# led_matrix_v_1_0.net
KiCad netlist of a schematic drawn in EAGLE
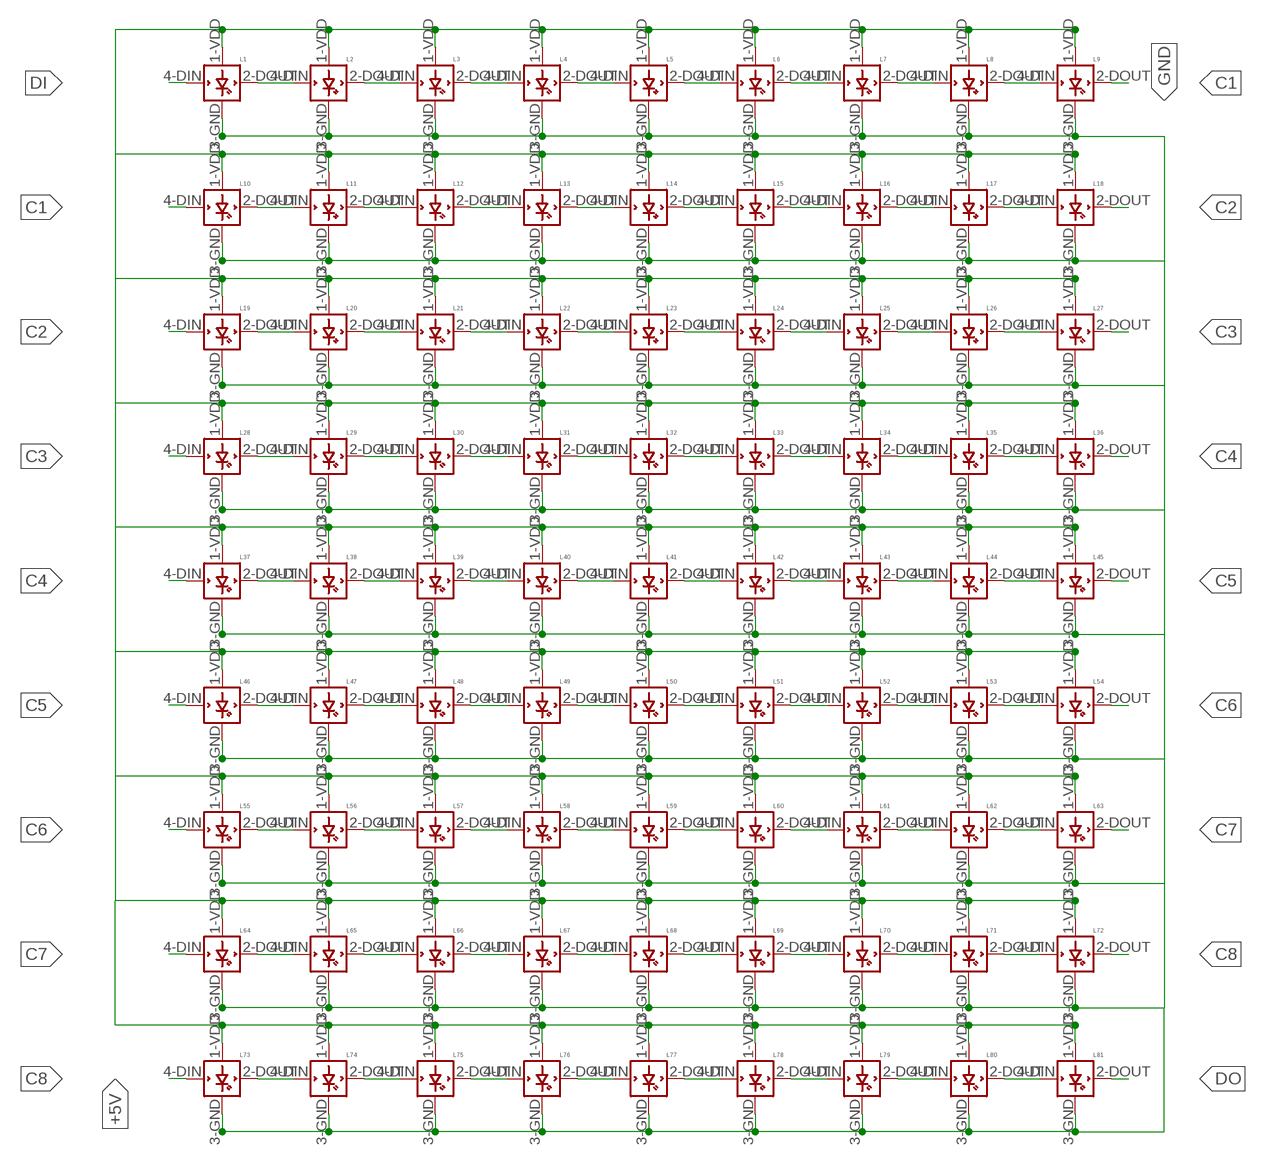
[diagram p0: schematic, sheet 1]

(export (version "E")
  (design (tool "Eeschema 10.0.6"))
  (components
    (comp (ref "L1")
      (value "WS2812B")
      (footprint "eagle-import:WS2812B")
      (libsource (lib "eagle-import") (part "WS2812B"))
    )
    (comp (ref "L2")
      (value "WS2812B")
      (footprint "eagle-import:WS2812B")
      (libsource (lib "eagle-import") (part "WS2812B"))
    )
    (comp (ref "L3")
      (value "WS2812B")
      (footprint "eagle-import:WS2812B")
      (libsource (lib "eagle-import") (part "WS2812B"))
    )
    (comp (ref "L4")
      (value "WS2812B")
      (footprint "eagle-import:WS2812B")
      (libsource (lib "eagle-import") (part "WS2812B"))
    )
    (comp (ref "L5")
      (value "WS2812B")
      (footprint "eagle-import:WS2812B")
      (libsource (lib "eagle-import") (part "WS2812B"))
    )
    (comp (ref "L6")
      (value "WS2812B")
      (footprint "eagle-import:WS2812B")
      (libsource (lib "eagle-import") (part "WS2812B"))
    )
    (comp (ref "L7")
      (value "WS2812B")
      (footprint "eagle-import:WS2812B")
      (libsource (lib "eagle-import") (part "WS2812B"))
    )
    (comp (ref "L8")
      (value "WS2812B")
      (footprint "eagle-import:WS2812B")
      (libsource (lib "eagle-import") (part "WS2812B"))
    )
    (comp (ref "L9")
      (value "WS2812B")
      (footprint "eagle-import:WS2812B")
      (libsource (lib "eagle-import") (part "WS2812B"))
    )
    (comp (ref "L10")
      (value "WS2812B")
      (footprint "eagle-import:WS2812B")
      (libsource (lib "eagle-import") (part "WS2812B"))
    )
    (comp (ref "L11")
      (value "WS2812B")
      (footprint "eagle-import:WS2812B")
      (libsource (lib "eagle-import") (part "WS2812B"))
    )
    (comp (ref "L12")
      (value "WS2812B")
      (footprint "eagle-import:WS2812B")
      (libsource (lib "eagle-import") (part "WS2812B"))
    )
    (comp (ref "L13")
      (value "WS2812B")
      (footprint "eagle-import:WS2812B")
      (libsource (lib "eagle-import") (part "WS2812B"))
    )
    (comp (ref "L14")
      (value "WS2812B")
      (footprint "eagle-import:WS2812B")
      (libsource (lib "eagle-import") (part "WS2812B"))
    )
    (comp (ref "L15")
      (value "WS2812B")
      (footprint "eagle-import:WS2812B")
      (libsource (lib "eagle-import") (part "WS2812B"))
    )
    (comp (ref "L16")
      (value "WS2812B")
      (footprint "eagle-import:WS2812B")
      (libsource (lib "eagle-import") (part "WS2812B"))
    )
    (comp (ref "L17")
      (value "WS2812B")
      (footprint "eagle-import:WS2812B")
      (libsource (lib "eagle-import") (part "WS2812B"))
    )
    (comp (ref "L18")
      (value "WS2812B")
      (footprint "eagle-import:WS2812B")
      (libsource (lib "eagle-import") (part "WS2812B"))
    )
    (comp (ref "L19")
      (value "WS2812B")
      (footprint "eagle-import:WS2812B")
      (libsource (lib "eagle-import") (part "WS2812B"))
    )
    (comp (ref "L20")
      (value "WS2812B")
      (footprint "eagle-import:WS2812B")
      (libsource (lib "eagle-import") (part "WS2812B"))
    )
    (comp (ref "L21")
      (value "WS2812B")
      (footprint "eagle-import:WS2812B")
      (libsource (lib "eagle-import") (part "WS2812B"))
    )
    (comp (ref "L22")
      (value "WS2812B")
      (footprint "eagle-import:WS2812B")
      (libsource (lib "eagle-import") (part "WS2812B"))
    )
    (comp (ref "L23")
      (value "WS2812B")
      (footprint "eagle-import:WS2812B")
      (libsource (lib "eagle-import") (part "WS2812B"))
    )
    (comp (ref "L24")
      (value "WS2812B")
      (footprint "eagle-import:WS2812B")
      (libsource (lib "eagle-import") (part "WS2812B"))
    )
    (comp (ref "L25")
      (value "WS2812B")
      (footprint "eagle-import:WS2812B")
      (libsource (lib "eagle-import") (part "WS2812B"))
    )
    (comp (ref "L26")
      (value "WS2812B")
      (footprint "eagle-import:WS2812B")
      (libsource (lib "eagle-import") (part "WS2812B"))
    )
    (comp (ref "L27")
      (value "WS2812B")
      (footprint "eagle-import:WS2812B")
      (libsource (lib "eagle-import") (part "WS2812B"))
    )
    (comp (ref "L28")
      (value "WS2812B")
      (footprint "eagle-import:WS2812B")
      (libsource (lib "eagle-import") (part "WS2812B"))
    )
    (comp (ref "L29")
      (value "WS2812B")
      (footprint "eagle-import:WS2812B")
      (libsource (lib "eagle-import") (part "WS2812B"))
    )
    (comp (ref "L30")
      (value "WS2812B")
      (footprint "eagle-import:WS2812B")
      (libsource (lib "eagle-import") (part "WS2812B"))
    )
    (comp (ref "L31")
      (value "WS2812B")
      (footprint "eagle-import:WS2812B")
      (libsource (lib "eagle-import") (part "WS2812B"))
    )
    (comp (ref "L32")
      (value "WS2812B")
      (footprint "eagle-import:WS2812B")
      (libsource (lib "eagle-import") (part "WS2812B"))
    )
    (comp (ref "L33")
      (value "WS2812B")
      (footprint "eagle-import:WS2812B")
      (libsource (lib "eagle-import") (part "WS2812B"))
    )
    (comp (ref "L34")
      (value "WS2812B")
      (footprint "eagle-import:WS2812B")
      (libsource (lib "eagle-import") (part "WS2812B"))
    )
    (comp (ref "L35")
      (value "WS2812B")
      (footprint "eagle-import:WS2812B")
      (libsource (lib "eagle-import") (part "WS2812B"))
    )
    (comp (ref "L36")
      (value "WS2812B")
      (footprint "eagle-import:WS2812B")
      (libsource (lib "eagle-import") (part "WS2812B"))
    )
    (comp (ref "L37")
      (value "WS2812B")
      (footprint "eagle-import:WS2812B")
      (libsource (lib "eagle-import") (part "WS2812B"))
    )
    (comp (ref "L38")
      (value "WS2812B")
      (footprint "eagle-import:WS2812B")
      (libsource (lib "eagle-import") (part "WS2812B"))
    )
    (comp (ref "L39")
      (value "WS2812B")
      (footprint "eagle-import:WS2812B")
      (libsource (lib "eagle-import") (part "WS2812B"))
    )
    (comp (ref "L40")
      (value "WS2812B")
      (footprint "eagle-import:WS2812B")
      (libsource (lib "eagle-import") (part "WS2812B"))
    )
    (comp (ref "L41")
      (value "WS2812B")
      (footprint "eagle-import:WS2812B")
      (libsource (lib "eagle-import") (part "WS2812B"))
    )
    (comp (ref "L42")
      (value "WS2812B")
      (footprint "eagle-import:WS2812B")
      (libsource (lib "eagle-import") (part "WS2812B"))
    )
    (comp (ref "L43")
      (value "WS2812B")
      (footprint "eagle-import:WS2812B")
      (libsource (lib "eagle-import") (part "WS2812B"))
    )
    (comp (ref "L44")
      (value "WS2812B")
      (footprint "eagle-import:WS2812B")
      (libsource (lib "eagle-import") (part "WS2812B"))
    )
    (comp (ref "L45")
      (value "WS2812B")
      (footprint "eagle-import:WS2812B")
      (libsource (lib "eagle-import") (part "WS2812B"))
    )
    (comp (ref "L46")
      (value "WS2812B")
      (footprint "eagle-import:WS2812B")
      (libsource (lib "eagle-import") (part "WS2812B"))
    )
    (comp (ref "L47")
      (value "WS2812B")
      (footprint "eagle-import:WS2812B")
      (libsource (lib "eagle-import") (part "WS2812B"))
    )
    (comp (ref "L48")
      (value "WS2812B")
      (footprint "eagle-import:WS2812B")
      (libsource (lib "eagle-import") (part "WS2812B"))
    )
    (comp (ref "L49")
      (value "WS2812B")
      (footprint "eagle-import:WS2812B")
      (libsource (lib "eagle-import") (part "WS2812B"))
    )
    (comp (ref "L50")
      (value "WS2812B")
      (footprint "eagle-import:WS2812B")
      (libsource (lib "eagle-import") (part "WS2812B"))
    )
    (comp (ref "L51")
      (value "WS2812B")
      (footprint "eagle-import:WS2812B")
      (libsource (lib "eagle-import") (part "WS2812B"))
    )
    (comp (ref "L52")
      (value "WS2812B")
      (footprint "eagle-import:WS2812B")
      (libsource (lib "eagle-import") (part "WS2812B"))
    )
    (comp (ref "L53")
      (value "WS2812B")
      (footprint "eagle-import:WS2812B")
      (libsource (lib "eagle-import") (part "WS2812B"))
    )
    (comp (ref "L54")
      (value "WS2812B")
      (footprint "eagle-import:WS2812B")
      (libsource (lib "eagle-import") (part "WS2812B"))
    )
    (comp (ref "L55")
      (value "WS2812B")
      (footprint "eagle-import:WS2812B")
      (libsource (lib "eagle-import") (part "WS2812B"))
    )
    (comp (ref "L56")
      (value "WS2812B")
      (footprint "eagle-import:WS2812B")
      (libsource (lib "eagle-import") (part "WS2812B"))
    )
    (comp (ref "L57")
      (value "WS2812B")
      (footprint "eagle-import:WS2812B")
      (libsource (lib "eagle-import") (part "WS2812B"))
    )
    (comp (ref "L58")
      (value "WS2812B")
      (footprint "eagle-import:WS2812B")
      (libsource (lib "eagle-import") (part "WS2812B"))
    )
    (comp (ref "L59")
      (value "WS2812B")
      (footprint "eagle-import:WS2812B")
      (libsource (lib "eagle-import") (part "WS2812B"))
    )
    (comp (ref "L60")
      (value "WS2812B")
      (footprint "eagle-import:WS2812B")
      (libsource (lib "eagle-import") (part "WS2812B"))
    )
    (comp (ref "L61")
      (value "WS2812B")
      (footprint "eagle-import:WS2812B")
      (libsource (lib "eagle-import") (part "WS2812B"))
    )
    (comp (ref "L62")
      (value "WS2812B")
      (footprint "eagle-import:WS2812B")
      (libsource (lib "eagle-import") (part "WS2812B"))
    )
    (comp (ref "L63")
      (value "WS2812B")
      (footprint "eagle-import:WS2812B")
      (libsource (lib "eagle-import") (part "WS2812B"))
    )
    (comp (ref "L64")
      (value "WS2812B")
      (footprint "eagle-import:WS2812B")
      (libsource (lib "eagle-import") (part "WS2812B"))
    )
    (comp (ref "L65")
      (value "WS2812B")
      (footprint "eagle-import:WS2812B")
      (libsource (lib "eagle-import") (part "WS2812B"))
    )
    (comp (ref "L66")
      (value "WS2812B")
      (footprint "eagle-import:WS2812B")
      (libsource (lib "eagle-import") (part "WS2812B"))
    )
    (comp (ref "L67")
      (value "WS2812B")
      (footprint "eagle-import:WS2812B")
      (libsource (lib "eagle-import") (part "WS2812B"))
    )
    (comp (ref "L68")
      (value "WS2812B")
      (footprint "eagle-import:WS2812B")
      (libsource (lib "eagle-import") (part "WS2812B"))
    )
    (comp (ref "L69")
      (value "WS2812B")
      (footprint "eagle-import:WS2812B")
      (libsource (lib "eagle-import") (part "WS2812B"))
    )
    (comp (ref "L70")
      (value "WS2812B")
      (footprint "eagle-import:WS2812B")
      (libsource (lib "eagle-import") (part "WS2812B"))
    )
    (comp (ref "L71")
      (value "WS2812B")
      (footprint "eagle-import:WS2812B")
      (libsource (lib "eagle-import") (part "WS2812B"))
    )
    (comp (ref "L72")
      (value "WS2812B")
      (footprint "eagle-import:WS2812B")
      (libsource (lib "eagle-import") (part "WS2812B"))
    )
    (comp (ref "L73")
      (value "WS2812B")
      (footprint "eagle-import:WS2812B")
      (libsource (lib "eagle-import") (part "WS2812B"))
    )
    (comp (ref "L74")
      (value "WS2812B")
      (footprint "eagle-import:WS2812B")
      (libsource (lib "eagle-import") (part "WS2812B"))
    )
    (comp (ref "L75")
      (value "WS2812B")
      (footprint "eagle-import:WS2812B")
      (libsource (lib "eagle-import") (part "WS2812B"))
    )
    (comp (ref "L76")
      (value "WS2812B")
      (footprint "eagle-import:WS2812B")
      (libsource (lib "eagle-import") (part "WS2812B"))
    )
    (comp (ref "L77")
      (value "WS2812B")
      (footprint "eagle-import:WS2812B")
      (libsource (lib "eagle-import") (part "WS2812B"))
    )
    (comp (ref "L78")
      (value "WS2812B")
      (footprint "eagle-import:WS2812B")
      (libsource (lib "eagle-import") (part "WS2812B"))
    )
    (comp (ref "L79")
      (value "WS2812B")
      (footprint "eagle-import:WS2812B")
      (libsource (lib "eagle-import") (part "WS2812B"))
    )
    (comp (ref "L80")
      (value "WS2812B")
      (footprint "eagle-import:WS2812B")
      (libsource (lib "eagle-import") (part "WS2812B"))
    )
    (comp (ref "L81")
      (value "WS2812B")
      (footprint "eagle-import:WS2812B")
      (libsource (lib "eagle-import") (part "WS2812B"))
    )
  )
  (nets
    (net (code "1") (name "+5V") (class "Default")
      (node (ref "L1") (pin "1-VDD") (pinfunction "VDD_1-VDD") (pintype "bidirectional"))
      (node (ref "L10") (pin "1-VDD") (pinfunction "VDD_1-VDD") (pintype "bidirectional"))
      (node (ref "L11") (pin "1-VDD") (pinfunction "VDD_1-VDD") (pintype "bidirectional"))
      (node (ref "L12") (pin "1-VDD") (pinfunction "VDD_1-VDD") (pintype "bidirectional"))
      (node (ref "L13") (pin "1-VDD") (pinfunction "VDD_1-VDD") (pintype "bidirectional"))
      (node (ref "L14") (pin "1-VDD") (pinfunction "VDD_1-VDD") (pintype "bidirectional"))
      (node (ref "L15") (pin "1-VDD") (pinfunction "VDD_1-VDD") (pintype "bidirectional"))
      (node (ref "L16") (pin "1-VDD") (pinfunction "VDD_1-VDD") (pintype "bidirectional"))
      (node (ref "L17") (pin "1-VDD") (pinfunction "VDD_1-VDD") (pintype "bidirectional"))
      (node (ref "L18") (pin "1-VDD") (pinfunction "VDD_1-VDD") (pintype "bidirectional"))
      (node (ref "L19") (pin "1-VDD") (pinfunction "VDD_1-VDD") (pintype "bidirectional"))
      (node (ref "L2") (pin "1-VDD") (pinfunction "VDD_1-VDD") (pintype "bidirectional"))
      (node (ref "L20") (pin "1-VDD") (pinfunction "VDD_1-VDD") (pintype "bidirectional"))
      (node (ref "L21") (pin "1-VDD") (pinfunction "VDD_1-VDD") (pintype "bidirectional"))
      (node (ref "L22") (pin "1-VDD") (pinfunction "VDD_1-VDD") (pintype "bidirectional"))
      (node (ref "L23") (pin "1-VDD") (pinfunction "VDD_1-VDD") (pintype "bidirectional"))
      (node (ref "L24") (pin "1-VDD") (pinfunction "VDD_1-VDD") (pintype "bidirectional"))
      (node (ref "L25") (pin "1-VDD") (pinfunction "VDD_1-VDD") (pintype "bidirectional"))
      (node (ref "L26") (pin "1-VDD") (pinfunction "VDD_1-VDD") (pintype "bidirectional"))
      (node (ref "L27") (pin "1-VDD") (pinfunction "VDD_1-VDD") (pintype "bidirectional"))
      (node (ref "L28") (pin "1-VDD") (pinfunction "VDD_1-VDD") (pintype "bidirectional"))
      (node (ref "L29") (pin "1-VDD") (pinfunction "VDD_1-VDD") (pintype "bidirectional"))
      (node (ref "L3") (pin "1-VDD") (pinfunction "VDD_1-VDD") (pintype "bidirectional"))
      (node (ref "L30") (pin "1-VDD") (pinfunction "VDD_1-VDD") (pintype "bidirectional"))
      (node (ref "L31") (pin "1-VDD") (pinfunction "VDD_1-VDD") (pintype "bidirectional"))
      (node (ref "L32") (pin "1-VDD") (pinfunction "VDD_1-VDD") (pintype "bidirectional"))
      (node (ref "L33") (pin "1-VDD") (pinfunction "VDD_1-VDD") (pintype "bidirectional"))
      (node (ref "L34") (pin "1-VDD") (pinfunction "VDD_1-VDD") (pintype "bidirectional"))
      (node (ref "L35") (pin "1-VDD") (pinfunction "VDD_1-VDD") (pintype "bidirectional"))
      (node (ref "L36") (pin "1-VDD") (pinfunction "VDD_1-VDD") (pintype "bidirectional"))
      (node (ref "L37") (pin "1-VDD") (pinfunction "VDD_1-VDD") (pintype "bidirectional"))
      (node (ref "L38") (pin "1-VDD") (pinfunction "VDD_1-VDD") (pintype "bidirectional"))
      (node (ref "L39") (pin "1-VDD") (pinfunction "VDD_1-VDD") (pintype "bidirectional"))
      (node (ref "L4") (pin "1-VDD") (pinfunction "VDD_1-VDD") (pintype "bidirectional"))
      (node (ref "L40") (pin "1-VDD") (pinfunction "VDD_1-VDD") (pintype "bidirectional"))
      (node (ref "L41") (pin "1-VDD") (pinfunction "VDD_1-VDD") (pintype "bidirectional"))
      (node (ref "L42") (pin "1-VDD") (pinfunction "VDD_1-VDD") (pintype "bidirectional"))
      (node (ref "L43") (pin "1-VDD") (pinfunction "VDD_1-VDD") (pintype "bidirectional"))
      (node (ref "L44") (pin "1-VDD") (pinfunction "VDD_1-VDD") (pintype "bidirectional"))
      (node (ref "L45") (pin "1-VDD") (pinfunction "VDD_1-VDD") (pintype "bidirectional"))
      (node (ref "L46") (pin "1-VDD") (pinfunction "VDD_1-VDD") (pintype "bidirectional"))
      (node (ref "L47") (pin "1-VDD") (pinfunction "VDD_1-VDD") (pintype "bidirectional"))
      (node (ref "L48") (pin "1-VDD") (pinfunction "VDD_1-VDD") (pintype "bidirectional"))
      (node (ref "L49") (pin "1-VDD") (pinfunction "VDD_1-VDD") (pintype "bidirectional"))
      (node (ref "L5") (pin "1-VDD") (pinfunction "VDD_1-VDD") (pintype "bidirectional"))
      (node (ref "L50") (pin "1-VDD") (pinfunction "VDD_1-VDD") (pintype "bidirectional"))
      (node (ref "L51") (pin "1-VDD") (pinfunction "VDD_1-VDD") (pintype "bidirectional"))
      (node (ref "L52") (pin "1-VDD") (pinfunction "VDD_1-VDD") (pintype "bidirectional"))
      (node (ref "L53") (pin "1-VDD") (pinfunction "VDD_1-VDD") (pintype "bidirectional"))
      (node (ref "L54") (pin "1-VDD") (pinfunction "VDD_1-VDD") (pintype "bidirectional"))
      (node (ref "L55") (pin "1-VDD") (pinfunction "VDD_1-VDD") (pintype "bidirectional"))
      (node (ref "L56") (pin "1-VDD") (pinfunction "VDD_1-VDD") (pintype "bidirectional"))
      (node (ref "L57") (pin "1-VDD") (pinfunction "VDD_1-VDD") (pintype "bidirectional"))
      (node (ref "L58") (pin "1-VDD") (pinfunction "VDD_1-VDD") (pintype "bidirectional"))
      (node (ref "L59") (pin "1-VDD") (pinfunction "VDD_1-VDD") (pintype "bidirectional"))
      (node (ref "L6") (pin "1-VDD") (pinfunction "VDD_1-VDD") (pintype "bidirectional"))
      (node (ref "L60") (pin "1-VDD") (pinfunction "VDD_1-VDD") (pintype "bidirectional"))
      (node (ref "L61") (pin "1-VDD") (pinfunction "VDD_1-VDD") (pintype "bidirectional"))
      (node (ref "L62") (pin "1-VDD") (pinfunction "VDD_1-VDD") (pintype "bidirectional"))
      (node (ref "L63") (pin "1-VDD") (pinfunction "VDD_1-VDD") (pintype "bidirectional"))
      (node (ref "L64") (pin "1-VDD") (pinfunction "VDD_1-VDD") (pintype "bidirectional"))
      (node (ref "L65") (pin "1-VDD") (pinfunction "VDD_1-VDD") (pintype "bidirectional"))
      (node (ref "L66") (pin "1-VDD") (pinfunction "VDD_1-VDD") (pintype "bidirectional"))
      (node (ref "L67") (pin "1-VDD") (pinfunction "VDD_1-VDD") (pintype "bidirectional"))
      (node (ref "L68") (pin "1-VDD") (pinfunction "VDD_1-VDD") (pintype "bidirectional"))
      (node (ref "L69") (pin "1-VDD") (pinfunction "VDD_1-VDD") (pintype "bidirectional"))
      (node (ref "L7") (pin "1-VDD") (pinfunction "VDD_1-VDD") (pintype "bidirectional"))
      (node (ref "L70") (pin "1-VDD") (pinfunction "VDD_1-VDD") (pintype "bidirectional"))
      (node (ref "L71") (pin "1-VDD") (pinfunction "VDD_1-VDD") (pintype "bidirectional"))
      (node (ref "L72") (pin "1-VDD") (pinfunction "VDD_1-VDD") (pintype "bidirectional"))
      (node (ref "L73") (pin "1-VDD") (pinfunction "VDD_1-VDD") (pintype "bidirectional"))
      (node (ref "L74") (pin "1-VDD") (pinfunction "VDD_1-VDD") (pintype "bidirectional"))
      (node (ref "L75") (pin "1-VDD") (pinfunction "VDD_1-VDD") (pintype "bidirectional"))
      (node (ref "L76") (pin "1-VDD") (pinfunction "VDD_1-VDD") (pintype "bidirectional"))
      (node (ref "L77") (pin "1-VDD") (pinfunction "VDD_1-VDD") (pintype "bidirectional"))
      (node (ref "L78") (pin "1-VDD") (pinfunction "VDD_1-VDD") (pintype "bidirectional"))
      (node (ref "L79") (pin "1-VDD") (pinfunction "VDD_1-VDD") (pintype "bidirectional"))
      (node (ref "L8") (pin "1-VDD") (pinfunction "VDD_1-VDD") (pintype "bidirectional"))
      (node (ref "L80") (pin "1-VDD") (pinfunction "VDD_1-VDD") (pintype "bidirectional"))
      (node (ref "L81") (pin "1-VDD") (pinfunction "VDD_1-VDD") (pintype "bidirectional"))
      (node (ref "L9") (pin "1-VDD") (pinfunction "VDD_1-VDD") (pintype "bidirectional"))
    )
    (net (code "2") (name "C1") (class "Default")
      (node (ref "L10") (pin "4-DIN") (pinfunction "DIN_4-DIN") (pintype "input"))
      (node (ref "L9") (pin "2-DOUT") (pinfunction "DOUT_2-DOUT") (pintype "output"))
    )
    (net (code "3") (name "C2") (class "Default")
      (node (ref "L18") (pin "2-DOUT") (pinfunction "DOUT_2-DOUT") (pintype "output"))
      (node (ref "L19") (pin "4-DIN") (pinfunction "DIN_4-DIN") (pintype "input"))
    )
    (net (code "4") (name "C3") (class "Default")
      (node (ref "L27") (pin "2-DOUT") (pinfunction "DOUT_2-DOUT") (pintype "output"))
      (node (ref "L28") (pin "4-DIN") (pinfunction "DIN_4-DIN") (pintype "input"))
    )
    (net (code "5") (name "C4") (class "Default")
      (node (ref "L36") (pin "2-DOUT") (pinfunction "DOUT_2-DOUT") (pintype "output"))
      (node (ref "L37") (pin "4-DIN") (pinfunction "DIN_4-DIN") (pintype "input"))
    )
    (net (code "6") (name "C5") (class "Default")
      (node (ref "L45") (pin "2-DOUT") (pinfunction "DOUT_2-DOUT") (pintype "output"))
      (node (ref "L46") (pin "4-DIN") (pinfunction "DIN_4-DIN") (pintype "input"))
    )
    (net (code "7") (name "C6") (class "Default")
      (node (ref "L54") (pin "2-DOUT") (pinfunction "DOUT_2-DOUT") (pintype "output"))
      (node (ref "L55") (pin "4-DIN") (pinfunction "DIN_4-DIN") (pintype "input"))
    )
    (net (code "8") (name "C7") (class "Default")
      (node (ref "L63") (pin "2-DOUT") (pinfunction "DOUT_2-DOUT") (pintype "output"))
      (node (ref "L64") (pin "4-DIN") (pinfunction "DIN_4-DIN") (pintype "input"))
    )
    (net (code "9") (name "C8") (class "Default")
      (node (ref "L72") (pin "2-DOUT") (pinfunction "DOUT_2-DOUT") (pintype "output"))
      (node (ref "L73") (pin "4-DIN") (pinfunction "DIN_4-DIN") (pintype "input"))
    )
    (net (code "10") (name "DI") (class "Default")
      (node (ref "L1") (pin "4-DIN") (pinfunction "DIN_4-DIN") (pintype "input"))
    )
    (net (code "11") (name "DO") (class "Default")
      (node (ref "L81") (pin "2-DOUT") (pinfunction "DOUT_2-DOUT") (pintype "output"))
    )
    (net (code "12") (name "GND") (class "Default")
      (node (ref "L1") (pin "3-GND") (pinfunction "GND_3-GND") (pintype "bidirectional"))
      (node (ref "L10") (pin "3-GND") (pinfunction "GND_3-GND") (pintype "bidirectional"))
      (node (ref "L11") (pin "3-GND") (pinfunction "GND_3-GND") (pintype "bidirectional"))
      (node (ref "L12") (pin "3-GND") (pinfunction "GND_3-GND") (pintype "bidirectional"))
      (node (ref "L13") (pin "3-GND") (pinfunction "GND_3-GND") (pintype "bidirectional"))
      (node (ref "L14") (pin "3-GND") (pinfunction "GND_3-GND") (pintype "bidirectional"))
      (node (ref "L15") (pin "3-GND") (pinfunction "GND_3-GND") (pintype "bidirectional"))
      (node (ref "L16") (pin "3-GND") (pinfunction "GND_3-GND") (pintype "bidirectional"))
      (node (ref "L17") (pin "3-GND") (pinfunction "GND_3-GND") (pintype "bidirectional"))
      (node (ref "L18") (pin "3-GND") (pinfunction "GND_3-GND") (pintype "bidirectional"))
      (node (ref "L19") (pin "3-GND") (pinfunction "GND_3-GND") (pintype "bidirectional"))
      (node (ref "L2") (pin "3-GND") (pinfunction "GND_3-GND") (pintype "bidirectional"))
      (node (ref "L20") (pin "3-GND") (pinfunction "GND_3-GND") (pintype "bidirectional"))
      (node (ref "L21") (pin "3-GND") (pinfunction "GND_3-GND") (pintype "bidirectional"))
      (node (ref "L22") (pin "3-GND") (pinfunction "GND_3-GND") (pintype "bidirectional"))
      (node (ref "L23") (pin "3-GND") (pinfunction "GND_3-GND") (pintype "bidirectional"))
      (node (ref "L24") (pin "3-GND") (pinfunction "GND_3-GND") (pintype "bidirectional"))
      (node (ref "L25") (pin "3-GND") (pinfunction "GND_3-GND") (pintype "bidirectional"))
      (node (ref "L26") (pin "3-GND") (pinfunction "GND_3-GND") (pintype "bidirectional"))
      (node (ref "L27") (pin "3-GND") (pinfunction "GND_3-GND") (pintype "bidirectional"))
      (node (ref "L28") (pin "3-GND") (pinfunction "GND_3-GND") (pintype "bidirectional"))
      (node (ref "L29") (pin "3-GND") (pinfunction "GND_3-GND") (pintype "bidirectional"))
      (node (ref "L3") (pin "3-GND") (pinfunction "GND_3-GND") (pintype "bidirectional"))
      (node (ref "L30") (pin "3-GND") (pinfunction "GND_3-GND") (pintype "bidirectional"))
      (node (ref "L31") (pin "3-GND") (pinfunction "GND_3-GND") (pintype "bidirectional"))
      (node (ref "L32") (pin "3-GND") (pinfunction "GND_3-GND") (pintype "bidirectional"))
      (node (ref "L33") (pin "3-GND") (pinfunction "GND_3-GND") (pintype "bidirectional"))
      (node (ref "L34") (pin "3-GND") (pinfunction "GND_3-GND") (pintype "bidirectional"))
      (node (ref "L35") (pin "3-GND") (pinfunction "GND_3-GND") (pintype "bidirectional"))
      (node (ref "L36") (pin "3-GND") (pinfunction "GND_3-GND") (pintype "bidirectional"))
      (node (ref "L37") (pin "3-GND") (pinfunction "GND_3-GND") (pintype "bidirectional"))
      (node (ref "L38") (pin "3-GND") (pinfunction "GND_3-GND") (pintype "bidirectional"))
      (node (ref "L39") (pin "3-GND") (pinfunction "GND_3-GND") (pintype "bidirectional"))
      (node (ref "L4") (pin "3-GND") (pinfunction "GND_3-GND") (pintype "bidirectional"))
      (node (ref "L40") (pin "3-GND") (pinfunction "GND_3-GND") (pintype "bidirectional"))
      (node (ref "L41") (pin "3-GND") (pinfunction "GND_3-GND") (pintype "bidirectional"))
      (node (ref "L42") (pin "3-GND") (pinfunction "GND_3-GND") (pintype "bidirectional"))
      (node (ref "L43") (pin "3-GND") (pinfunction "GND_3-GND") (pintype "bidirectional"))
      (node (ref "L44") (pin "3-GND") (pinfunction "GND_3-GND") (pintype "bidirectional"))
      (node (ref "L45") (pin "3-GND") (pinfunction "GND_3-GND") (pintype "bidirectional"))
      (node (ref "L46") (pin "3-GND") (pinfunction "GND_3-GND") (pintype "bidirectional"))
      (node (ref "L47") (pin "3-GND") (pinfunction "GND_3-GND") (pintype "bidirectional"))
      (node (ref "L48") (pin "3-GND") (pinfunction "GND_3-GND") (pintype "bidirectional"))
      (node (ref "L49") (pin "3-GND") (pinfunction "GND_3-GND") (pintype "bidirectional"))
      (node (ref "L5") (pin "3-GND") (pinfunction "GND_3-GND") (pintype "bidirectional"))
      (node (ref "L50") (pin "3-GND") (pinfunction "GND_3-GND") (pintype "bidirectional"))
      (node (ref "L51") (pin "3-GND") (pinfunction "GND_3-GND") (pintype "bidirectional"))
      (node (ref "L52") (pin "3-GND") (pinfunction "GND_3-GND") (pintype "bidirectional"))
      (node (ref "L53") (pin "3-GND") (pinfunction "GND_3-GND") (pintype "bidirectional"))
      (node (ref "L54") (pin "3-GND") (pinfunction "GND_3-GND") (pintype "bidirectional"))
      (node (ref "L55") (pin "3-GND") (pinfunction "GND_3-GND") (pintype "bidirectional"))
      (node (ref "L56") (pin "3-GND") (pinfunction "GND_3-GND") (pintype "bidirectional"))
      (node (ref "L57") (pin "3-GND") (pinfunction "GND_3-GND") (pintype "bidirectional"))
      (node (ref "L58") (pin "3-GND") (pinfunction "GND_3-GND") (pintype "bidirectional"))
      (node (ref "L59") (pin "3-GND") (pinfunction "GND_3-GND") (pintype "bidirectional"))
      (node (ref "L6") (pin "3-GND") (pinfunction "GND_3-GND") (pintype "bidirectional"))
      (node (ref "L60") (pin "3-GND") (pinfunction "GND_3-GND") (pintype "bidirectional"))
      (node (ref "L61") (pin "3-GND") (pinfunction "GND_3-GND") (pintype "bidirectional"))
      (node (ref "L62") (pin "3-GND") (pinfunction "GND_3-GND") (pintype "bidirectional"))
      (node (ref "L63") (pin "3-GND") (pinfunction "GND_3-GND") (pintype "bidirectional"))
      (node (ref "L64") (pin "3-GND") (pinfunction "GND_3-GND") (pintype "bidirectional"))
      (node (ref "L65") (pin "3-GND") (pinfunction "GND_3-GND") (pintype "bidirectional"))
      (node (ref "L66") (pin "3-GND") (pinfunction "GND_3-GND") (pintype "bidirectional"))
      (node (ref "L67") (pin "3-GND") (pinfunction "GND_3-GND") (pintype "bidirectional"))
      (node (ref "L68") (pin "3-GND") (pinfunction "GND_3-GND") (pintype "bidirectional"))
      (node (ref "L69") (pin "3-GND") (pinfunction "GND_3-GND") (pintype "bidirectional"))
      (node (ref "L7") (pin "3-GND") (pinfunction "GND_3-GND") (pintype "bidirectional"))
      (node (ref "L70") (pin "3-GND") (pinfunction "GND_3-GND") (pintype "bidirectional"))
      (node (ref "L71") (pin "3-GND") (pinfunction "GND_3-GND") (pintype "bidirectional"))
      (node (ref "L72") (pin "3-GND") (pinfunction "GND_3-GND") (pintype "bidirectional"))
      (node (ref "L73") (pin "3-GND") (pinfunction "GND_3-GND") (pintype "bidirectional"))
      (node (ref "L74") (pin "3-GND") (pinfunction "GND_3-GND") (pintype "bidirectional"))
      (node (ref "L75") (pin "3-GND") (pinfunction "GND_3-GND") (pintype "bidirectional"))
      (node (ref "L76") (pin "3-GND") (pinfunction "GND_3-GND") (pintype "bidirectional"))
      (node (ref "L77") (pin "3-GND") (pinfunction "GND_3-GND") (pintype "bidirectional"))
      (node (ref "L78") (pin "3-GND") (pinfunction "GND_3-GND") (pintype "bidirectional"))
      (node (ref "L79") (pin "3-GND") (pinfunction "GND_3-GND") (pintype "bidirectional"))
      (node (ref "L8") (pin "3-GND") (pinfunction "GND_3-GND") (pintype "bidirectional"))
      (node (ref "L80") (pin "3-GND") (pinfunction "GND_3-GND") (pintype "bidirectional"))
      (node (ref "L81") (pin "3-GND") (pinfunction "GND_3-GND") (pintype "bidirectional"))
      (node (ref "L9") (pin "3-GND") (pinfunction "GND_3-GND") (pintype "bidirectional"))
    )
    (net (code "13") (name "Net-(L1-DOUT)") (class "Default")
      (node (ref "L1") (pin "2-DOUT") (pinfunction "DOUT_2-DOUT") (pintype "output"))
      (node (ref "L2") (pin "4-DIN") (pinfunction "DIN_4-DIN") (pintype "input"))
    )
    (net (code "14") (name "Net-(L2-DOUT)") (class "Default")
      (node (ref "L2") (pin "2-DOUT") (pinfunction "DOUT_2-DOUT") (pintype "output"))
      (node (ref "L3") (pin "4-DIN") (pinfunction "DIN_4-DIN") (pintype "input"))
    )
    (net (code "15") (name "Net-(L3-DOUT)") (class "Default")
      (node (ref "L3") (pin "2-DOUT") (pinfunction "DOUT_2-DOUT") (pintype "output"))
      (node (ref "L4") (pin "4-DIN") (pinfunction "DIN_4-DIN") (pintype "input"))
    )
    (net (code "16") (name "Net-(L4-DOUT)") (class "Default")
      (node (ref "L4") (pin "2-DOUT") (pinfunction "DOUT_2-DOUT") (pintype "output"))
      (node (ref "L5") (pin "4-DIN") (pinfunction "DIN_4-DIN") (pintype "input"))
    )
    (net (code "17") (name "Net-(L5-DOUT)") (class "Default")
      (node (ref "L5") (pin "2-DOUT") (pinfunction "DOUT_2-DOUT") (pintype "output"))
      (node (ref "L6") (pin "4-DIN") (pinfunction "DIN_4-DIN") (pintype "input"))
    )
    (net (code "18") (name "Net-(L6-DOUT)") (class "Default")
      (node (ref "L6") (pin "2-DOUT") (pinfunction "DOUT_2-DOUT") (pintype "output"))
      (node (ref "L7") (pin "4-DIN") (pinfunction "DIN_4-DIN") (pintype "input"))
    )
    (net (code "19") (name "Net-(L7-DOUT)") (class "Default")
      (node (ref "L7") (pin "2-DOUT") (pinfunction "DOUT_2-DOUT") (pintype "output"))
      (node (ref "L8") (pin "4-DIN") (pinfunction "DIN_4-DIN") (pintype "input"))
    )
    (net (code "20") (name "Net-(L8-DOUT)") (class "Default")
      (node (ref "L8") (pin "2-DOUT") (pinfunction "DOUT_2-DOUT") (pintype "output"))
      (node (ref "L9") (pin "4-DIN") (pinfunction "DIN_4-DIN") (pintype "input"))
    )
    (net (code "21") (name "Net-(L10-DOUT)") (class "Default")
      (node (ref "L10") (pin "2-DOUT") (pinfunction "DOUT_2-DOUT") (pintype "output"))
      (node (ref "L11") (pin "4-DIN") (pinfunction "DIN_4-DIN") (pintype "input"))
    )
    (net (code "22") (name "Net-(L11-DOUT)") (class "Default")
      (node (ref "L11") (pin "2-DOUT") (pinfunction "DOUT_2-DOUT") (pintype "output"))
      (node (ref "L12") (pin "4-DIN") (pinfunction "DIN_4-DIN") (pintype "input"))
    )
    (net (code "23") (name "Net-(L12-DOUT)") (class "Default")
      (node (ref "L12") (pin "2-DOUT") (pinfunction "DOUT_2-DOUT") (pintype "output"))
      (node (ref "L13") (pin "4-DIN") (pinfunction "DIN_4-DIN") (pintype "input"))
    )
    (net (code "24") (name "Net-(L13-DOUT)") (class "Default")
      (node (ref "L13") (pin "2-DOUT") (pinfunction "DOUT_2-DOUT") (pintype "output"))
      (node (ref "L14") (pin "4-DIN") (pinfunction "DIN_4-DIN") (pintype "input"))
    )
    (net (code "25") (name "Net-(L14-DOUT)") (class "Default")
      (node (ref "L14") (pin "2-DOUT") (pinfunction "DOUT_2-DOUT") (pintype "output"))
      (node (ref "L15") (pin "4-DIN") (pinfunction "DIN_4-DIN") (pintype "input"))
    )
    (net (code "26") (name "Net-(L15-DOUT)") (class "Default")
      (node (ref "L15") (pin "2-DOUT") (pinfunction "DOUT_2-DOUT") (pintype "output"))
      (node (ref "L16") (pin "4-DIN") (pinfunction "DIN_4-DIN") (pintype "input"))
    )
    (net (code "27") (name "Net-(L16-DOUT)") (class "Default")
      (node (ref "L16") (pin "2-DOUT") (pinfunction "DOUT_2-DOUT") (pintype "output"))
      (node (ref "L17") (pin "4-DIN") (pinfunction "DIN_4-DIN") (pintype "input"))
    )
    (net (code "28") (name "Net-(L17-DOUT)") (class "Default")
      (node (ref "L17") (pin "2-DOUT") (pinfunction "DOUT_2-DOUT") (pintype "output"))
      (node (ref "L18") (pin "4-DIN") (pinfunction "DIN_4-DIN") (pintype "input"))
    )
    (net (code "29") (name "Net-(L19-DOUT)") (class "Default")
      (node (ref "L19") (pin "2-DOUT") (pinfunction "DOUT_2-DOUT") (pintype "output"))
      (node (ref "L20") (pin "4-DIN") (pinfunction "DIN_4-DIN") (pintype "input"))
    )
    (net (code "30") (name "Net-(L20-DOUT)") (class "Default")
      (node (ref "L20") (pin "2-DOUT") (pinfunction "DOUT_2-DOUT") (pintype "output"))
      (node (ref "L21") (pin "4-DIN") (pinfunction "DIN_4-DIN") (pintype "input"))
    )
    (net (code "31") (name "Net-(L21-DOUT)") (class "Default")
      (node (ref "L21") (pin "2-DOUT") (pinfunction "DOUT_2-DOUT") (pintype "output"))
      (node (ref "L22") (pin "4-DIN") (pinfunction "DIN_4-DIN") (pintype "input"))
    )
    (net (code "32") (name "Net-(L22-DOUT)") (class "Default")
      (node (ref "L22") (pin "2-DOUT") (pinfunction "DOUT_2-DOUT") (pintype "output"))
      (node (ref "L23") (pin "4-DIN") (pinfunction "DIN_4-DIN") (pintype "input"))
    )
    (net (code "33") (name "Net-(L23-DOUT)") (class "Default")
      (node (ref "L23") (pin "2-DOUT") (pinfunction "DOUT_2-DOUT") (pintype "output"))
      (node (ref "L24") (pin "4-DIN") (pinfunction "DIN_4-DIN") (pintype "input"))
    )
    (net (code "34") (name "Net-(L24-DOUT)") (class "Default")
      (node (ref "L24") (pin "2-DOUT") (pinfunction "DOUT_2-DOUT") (pintype "output"))
      (node (ref "L25") (pin "4-DIN") (pinfunction "DIN_4-DIN") (pintype "input"))
    )
    (net (code "35") (name "Net-(L25-DOUT)") (class "Default")
      (node (ref "L25") (pin "2-DOUT") (pinfunction "DOUT_2-DOUT") (pintype "output"))
      (node (ref "L26") (pin "4-DIN") (pinfunction "DIN_4-DIN") (pintype "input"))
    )
    (net (code "36") (name "Net-(L26-DOUT)") (class "Default")
      (node (ref "L26") (pin "2-DOUT") (pinfunction "DOUT_2-DOUT") (pintype "output"))
      (node (ref "L27") (pin "4-DIN") (pinfunction "DIN_4-DIN") (pintype "input"))
    )
    (net (code "37") (name "Net-(L28-DOUT)") (class "Default")
      (node (ref "L28") (pin "2-DOUT") (pinfunction "DOUT_2-DOUT") (pintype "output"))
      (node (ref "L29") (pin "4-DIN") (pinfunction "DIN_4-DIN") (pintype "input"))
    )
    (net (code "38") (name "Net-(L29-DOUT)") (class "Default")
      (node (ref "L29") (pin "2-DOUT") (pinfunction "DOUT_2-DOUT") (pintype "output"))
      (node (ref "L30") (pin "4-DIN") (pinfunction "DIN_4-DIN") (pintype "input"))
    )
    (net (code "39") (name "Net-(L30-DOUT)") (class "Default")
      (node (ref "L30") (pin "2-DOUT") (pinfunction "DOUT_2-DOUT") (pintype "output"))
      (node (ref "L31") (pin "4-DIN") (pinfunction "DIN_4-DIN") (pintype "input"))
    )
    (net (code "40") (name "Net-(L31-DOUT)") (class "Default")
      (node (ref "L31") (pin "2-DOUT") (pinfunction "DOUT_2-DOUT") (pintype "output"))
      (node (ref "L32") (pin "4-DIN") (pinfunction "DIN_4-DIN") (pintype "input"))
    )
    (net (code "41") (name "Net-(L32-DOUT)") (class "Default")
      (node (ref "L32") (pin "2-DOUT") (pinfunction "DOUT_2-DOUT") (pintype "output"))
      (node (ref "L33") (pin "4-DIN") (pinfunction "DIN_4-DIN") (pintype "input"))
    )
    (net (code "42") (name "Net-(L33-DOUT)") (class "Default")
      (node (ref "L33") (pin "2-DOUT") (pinfunction "DOUT_2-DOUT") (pintype "output"))
      (node (ref "L34") (pin "4-DIN") (pinfunction "DIN_4-DIN") (pintype "input"))
    )
    (net (code "43") (name "Net-(L34-DOUT)") (class "Default")
      (node (ref "L34") (pin "2-DOUT") (pinfunction "DOUT_2-DOUT") (pintype "output"))
      (node (ref "L35") (pin "4-DIN") (pinfunction "DIN_4-DIN") (pintype "input"))
    )
    (net (code "44") (name "Net-(L35-DOUT)") (class "Default")
      (node (ref "L35") (pin "2-DOUT") (pinfunction "DOUT_2-DOUT") (pintype "output"))
      (node (ref "L36") (pin "4-DIN") (pinfunction "DIN_4-DIN") (pintype "input"))
    )
    (net (code "45") (name "Net-(L37-DOUT)") (class "Default")
      (node (ref "L37") (pin "2-DOUT") (pinfunction "DOUT_2-DOUT") (pintype "output"))
      (node (ref "L38") (pin "4-DIN") (pinfunction "DIN_4-DIN") (pintype "input"))
    )
    (net (code "46") (name "Net-(L38-DOUT)") (class "Default")
      (node (ref "L38") (pin "2-DOUT") (pinfunction "DOUT_2-DOUT") (pintype "output"))
      (node (ref "L39") (pin "4-DIN") (pinfunction "DIN_4-DIN") (pintype "input"))
    )
    (net (code "47") (name "Net-(L39-DOUT)") (class "Default")
      (node (ref "L39") (pin "2-DOUT") (pinfunction "DOUT_2-DOUT") (pintype "output"))
      (node (ref "L40") (pin "4-DIN") (pinfunction "DIN_4-DIN") (pintype "input"))
    )
    (net (code "48") (name "Net-(L40-DOUT)") (class "Default")
      (node (ref "L40") (pin "2-DOUT") (pinfunction "DOUT_2-DOUT") (pintype "output"))
      (node (ref "L41") (pin "4-DIN") (pinfunction "DIN_4-DIN") (pintype "input"))
    )
    (net (code "49") (name "Net-(L41-DOUT)") (class "Default")
      (node (ref "L41") (pin "2-DOUT") (pinfunction "DOUT_2-DOUT") (pintype "output"))
      (node (ref "L42") (pin "4-DIN") (pinfunction "DIN_4-DIN") (pintype "input"))
    )
    (net (code "50") (name "Net-(L42-DOUT)") (class "Default")
      (node (ref "L42") (pin "2-DOUT") (pinfunction "DOUT_2-DOUT") (pintype "output"))
      (node (ref "L43") (pin "4-DIN") (pinfunction "DIN_4-DIN") (pintype "input"))
    )
    (net (code "51") (name "Net-(L43-DOUT)") (class "Default")
      (node (ref "L43") (pin "2-DOUT") (pinfunction "DOUT_2-DOUT") (pintype "output"))
      (node (ref "L44") (pin "4-DIN") (pinfunction "DIN_4-DIN") (pintype "input"))
    )
    (net (code "52") (name "Net-(L44-DOUT)") (class "Default")
      (node (ref "L44") (pin "2-DOUT") (pinfunction "DOUT_2-DOUT") (pintype "output"))
      (node (ref "L45") (pin "4-DIN") (pinfunction "DIN_4-DIN") (pintype "input"))
    )
    (net (code "53") (name "Net-(L46-DOUT)") (class "Default")
      (node (ref "L46") (pin "2-DOUT") (pinfunction "DOUT_2-DOUT") (pintype "output"))
      (node (ref "L47") (pin "4-DIN") (pinfunction "DIN_4-DIN") (pintype "input"))
    )
    (net (code "54") (name "Net-(L47-DOUT)") (class "Default")
      (node (ref "L47") (pin "2-DOUT") (pinfunction "DOUT_2-DOUT") (pintype "output"))
      (node (ref "L48") (pin "4-DIN") (pinfunction "DIN_4-DIN") (pintype "input"))
    )
    (net (code "55") (name "Net-(L48-DOUT)") (class "Default")
      (node (ref "L48") (pin "2-DOUT") (pinfunction "DOUT_2-DOUT") (pintype "output"))
      (node (ref "L49") (pin "4-DIN") (pinfunction "DIN_4-DIN") (pintype "input"))
    )
    (net (code "56") (name "Net-(L49-DOUT)") (class "Default")
      (node (ref "L49") (pin "2-DOUT") (pinfunction "DOUT_2-DOUT") (pintype "output"))
      (node (ref "L50") (pin "4-DIN") (pinfunction "DIN_4-DIN") (pintype "input"))
    )
    (net (code "57") (name "Net-(L50-DOUT)") (class "Default")
      (node (ref "L50") (pin "2-DOUT") (pinfunction "DOUT_2-DOUT") (pintype "output"))
      (node (ref "L51") (pin "4-DIN") (pinfunction "DIN_4-DIN") (pintype "input"))
    )
    (net (code "58") (name "Net-(L51-DOUT)") (class "Default")
      (node (ref "L51") (pin "2-DOUT") (pinfunction "DOUT_2-DOUT") (pintype "output"))
      (node (ref "L52") (pin "4-DIN") (pinfunction "DIN_4-DIN") (pintype "input"))
    )
    (net (code "59") (name "Net-(L52-DOUT)") (class "Default")
      (node (ref "L52") (pin "2-DOUT") (pinfunction "DOUT_2-DOUT") (pintype "output"))
      (node (ref "L53") (pin "4-DIN") (pinfunction "DIN_4-DIN") (pintype "input"))
    )
    (net (code "60") (name "Net-(L53-DOUT)") (class "Default")
      (node (ref "L53") (pin "2-DOUT") (pinfunction "DOUT_2-DOUT") (pintype "output"))
      (node (ref "L54") (pin "4-DIN") (pinfunction "DIN_4-DIN") (pintype "input"))
    )
    (net (code "61") (name "Net-(L55-DOUT)") (class "Default")
      (node (ref "L55") (pin "2-DOUT") (pinfunction "DOUT_2-DOUT") (pintype "output"))
      (node (ref "L56") (pin "4-DIN") (pinfunction "DIN_4-DIN") (pintype "input"))
    )
    (net (code "62") (name "Net-(L56-DOUT)") (class "Default")
      (node (ref "L56") (pin "2-DOUT") (pinfunction "DOUT_2-DOUT") (pintype "output"))
      (node (ref "L57") (pin "4-DIN") (pinfunction "DIN_4-DIN") (pintype "input"))
    )
    (net (code "63") (name "Net-(L57-DOUT)") (class "Default")
      (node (ref "L57") (pin "2-DOUT") (pinfunction "DOUT_2-DOUT") (pintype "output"))
      (node (ref "L58") (pin "4-DIN") (pinfunction "DIN_4-DIN") (pintype "input"))
    )
    (net (code "64") (name "Net-(L58-DOUT)") (class "Default")
      (node (ref "L58") (pin "2-DOUT") (pinfunction "DOUT_2-DOUT") (pintype "output"))
      (node (ref "L59") (pin "4-DIN") (pinfunction "DIN_4-DIN") (pintype "input"))
    )
    (net (code "65") (name "Net-(L59-DOUT)") (class "Default")
      (node (ref "L59") (pin "2-DOUT") (pinfunction "DOUT_2-DOUT") (pintype "output"))
      (node (ref "L60") (pin "4-DIN") (pinfunction "DIN_4-DIN") (pintype "input"))
    )
    (net (code "66") (name "Net-(L60-DOUT)") (class "Default")
      (node (ref "L60") (pin "2-DOUT") (pinfunction "DOUT_2-DOUT") (pintype "output"))
      (node (ref "L61") (pin "4-DIN") (pinfunction "DIN_4-DIN") (pintype "input"))
    )
    (net (code "67") (name "Net-(L61-DOUT)") (class "Default")
      (node (ref "L61") (pin "2-DOUT") (pinfunction "DOUT_2-DOUT") (pintype "output"))
      (node (ref "L62") (pin "4-DIN") (pinfunction "DIN_4-DIN") (pintype "input"))
    )
    (net (code "68") (name "Net-(L62-DOUT)") (class "Default")
      (node (ref "L62") (pin "2-DOUT") (pinfunction "DOUT_2-DOUT") (pintype "output"))
      (node (ref "L63") (pin "4-DIN") (pinfunction "DIN_4-DIN") (pintype "input"))
    )
    (net (code "69") (name "Net-(L64-DOUT)") (class "Default")
      (node (ref "L64") (pin "2-DOUT") (pinfunction "DOUT_2-DOUT") (pintype "output"))
      (node (ref "L65") (pin "4-DIN") (pinfunction "DIN_4-DIN") (pintype "input"))
    )
    (net (code "70") (name "Net-(L65-DOUT)") (class "Default")
      (node (ref "L65") (pin "2-DOUT") (pinfunction "DOUT_2-DOUT") (pintype "output"))
      (node (ref "L66") (pin "4-DIN") (pinfunction "DIN_4-DIN") (pintype "input"))
    )
    (net (code "71") (name "Net-(L66-DOUT)") (class "Default")
      (node (ref "L66") (pin "2-DOUT") (pinfunction "DOUT_2-DOUT") (pintype "output"))
      (node (ref "L67") (pin "4-DIN") (pinfunction "DIN_4-DIN") (pintype "input"))
    )
    (net (code "72") (name "Net-(L67-DOUT)") (class "Default")
      (node (ref "L67") (pin "2-DOUT") (pinfunction "DOUT_2-DOUT") (pintype "output"))
      (node (ref "L68") (pin "4-DIN") (pinfunction "DIN_4-DIN") (pintype "input"))
    )
    (net (code "73") (name "Net-(L68-DOUT)") (class "Default")
      (node (ref "L68") (pin "2-DOUT") (pinfunction "DOUT_2-DOUT") (pintype "output"))
      (node (ref "L69") (pin "4-DIN") (pinfunction "DIN_4-DIN") (pintype "input"))
    )
    (net (code "74") (name "Net-(L69-DOUT)") (class "Default")
      (node (ref "L69") (pin "2-DOUT") (pinfunction "DOUT_2-DOUT") (pintype "output"))
      (node (ref "L70") (pin "4-DIN") (pinfunction "DIN_4-DIN") (pintype "input"))
    )
    (net (code "75") (name "Net-(L70-DOUT)") (class "Default")
      (node (ref "L70") (pin "2-DOUT") (pinfunction "DOUT_2-DOUT") (pintype "output"))
      (node (ref "L71") (pin "4-DIN") (pinfunction "DIN_4-DIN") (pintype "input"))
    )
    (net (code "76") (name "Net-(L71-DOUT)") (class "Default")
      (node (ref "L71") (pin "2-DOUT") (pinfunction "DOUT_2-DOUT") (pintype "output"))
      (node (ref "L72") (pin "4-DIN") (pinfunction "DIN_4-DIN") (pintype "input"))
    )
    (net (code "77") (name "Net-(L73-DOUT)") (class "Default")
      (node (ref "L73") (pin "2-DOUT") (pinfunction "DOUT_2-DOUT") (pintype "output"))
      (node (ref "L74") (pin "4-DIN") (pinfunction "DIN_4-DIN") (pintype "input"))
    )
    (net (code "78") (name "Net-(L74-DOUT)") (class "Default")
      (node (ref "L74") (pin "2-DOUT") (pinfunction "DOUT_2-DOUT") (pintype "output"))
      (node (ref "L75") (pin "4-DIN") (pinfunction "DIN_4-DIN") (pintype "input"))
    )
    (net (code "79") (name "Net-(L75-DOUT)") (class "Default")
      (node (ref "L75") (pin "2-DOUT") (pinfunction "DOUT_2-DOUT") (pintype "output"))
      (node (ref "L76") (pin "4-DIN") (pinfunction "DIN_4-DIN") (pintype "input"))
    )
    (net (code "80") (name "Net-(L76-DOUT)") (class "Default")
      (node (ref "L76") (pin "2-DOUT") (pinfunction "DOUT_2-DOUT") (pintype "output"))
      (node (ref "L77") (pin "4-DIN") (pinfunction "DIN_4-DIN") (pintype "input"))
    )
    (net (code "81") (name "Net-(L77-DOUT)") (class "Default")
      (node (ref "L77") (pin "2-DOUT") (pinfunction "DOUT_2-DOUT") (pintype "output"))
      (node (ref "L78") (pin "4-DIN") (pinfunction "DIN_4-DIN") (pintype "input"))
    )
    (net (code "82") (name "Net-(L78-DOUT)") (class "Default")
      (node (ref "L78") (pin "2-DOUT") (pinfunction "DOUT_2-DOUT") (pintype "output"))
      (node (ref "L79") (pin "4-DIN") (pinfunction "DIN_4-DIN") (pintype "input"))
    )
    (net (code "83") (name "Net-(L79-DOUT)") (class "Default")
      (node (ref "L79") (pin "2-DOUT") (pinfunction "DOUT_2-DOUT") (pintype "output"))
      (node (ref "L80") (pin "4-DIN") (pinfunction "DIN_4-DIN") (pintype "input"))
    )
    (net (code "84") (name "Net-(L80-DOUT)") (class "Default")
      (node (ref "L80") (pin "2-DOUT") (pinfunction "DOUT_2-DOUT") (pintype "output"))
      (node (ref "L81") (pin "4-DIN") (pinfunction "DIN_4-DIN") (pintype "input"))
    )
  )
)
